# Un_51_V2_0.net
KiCad netlist of a schematic drawn in EAGLE
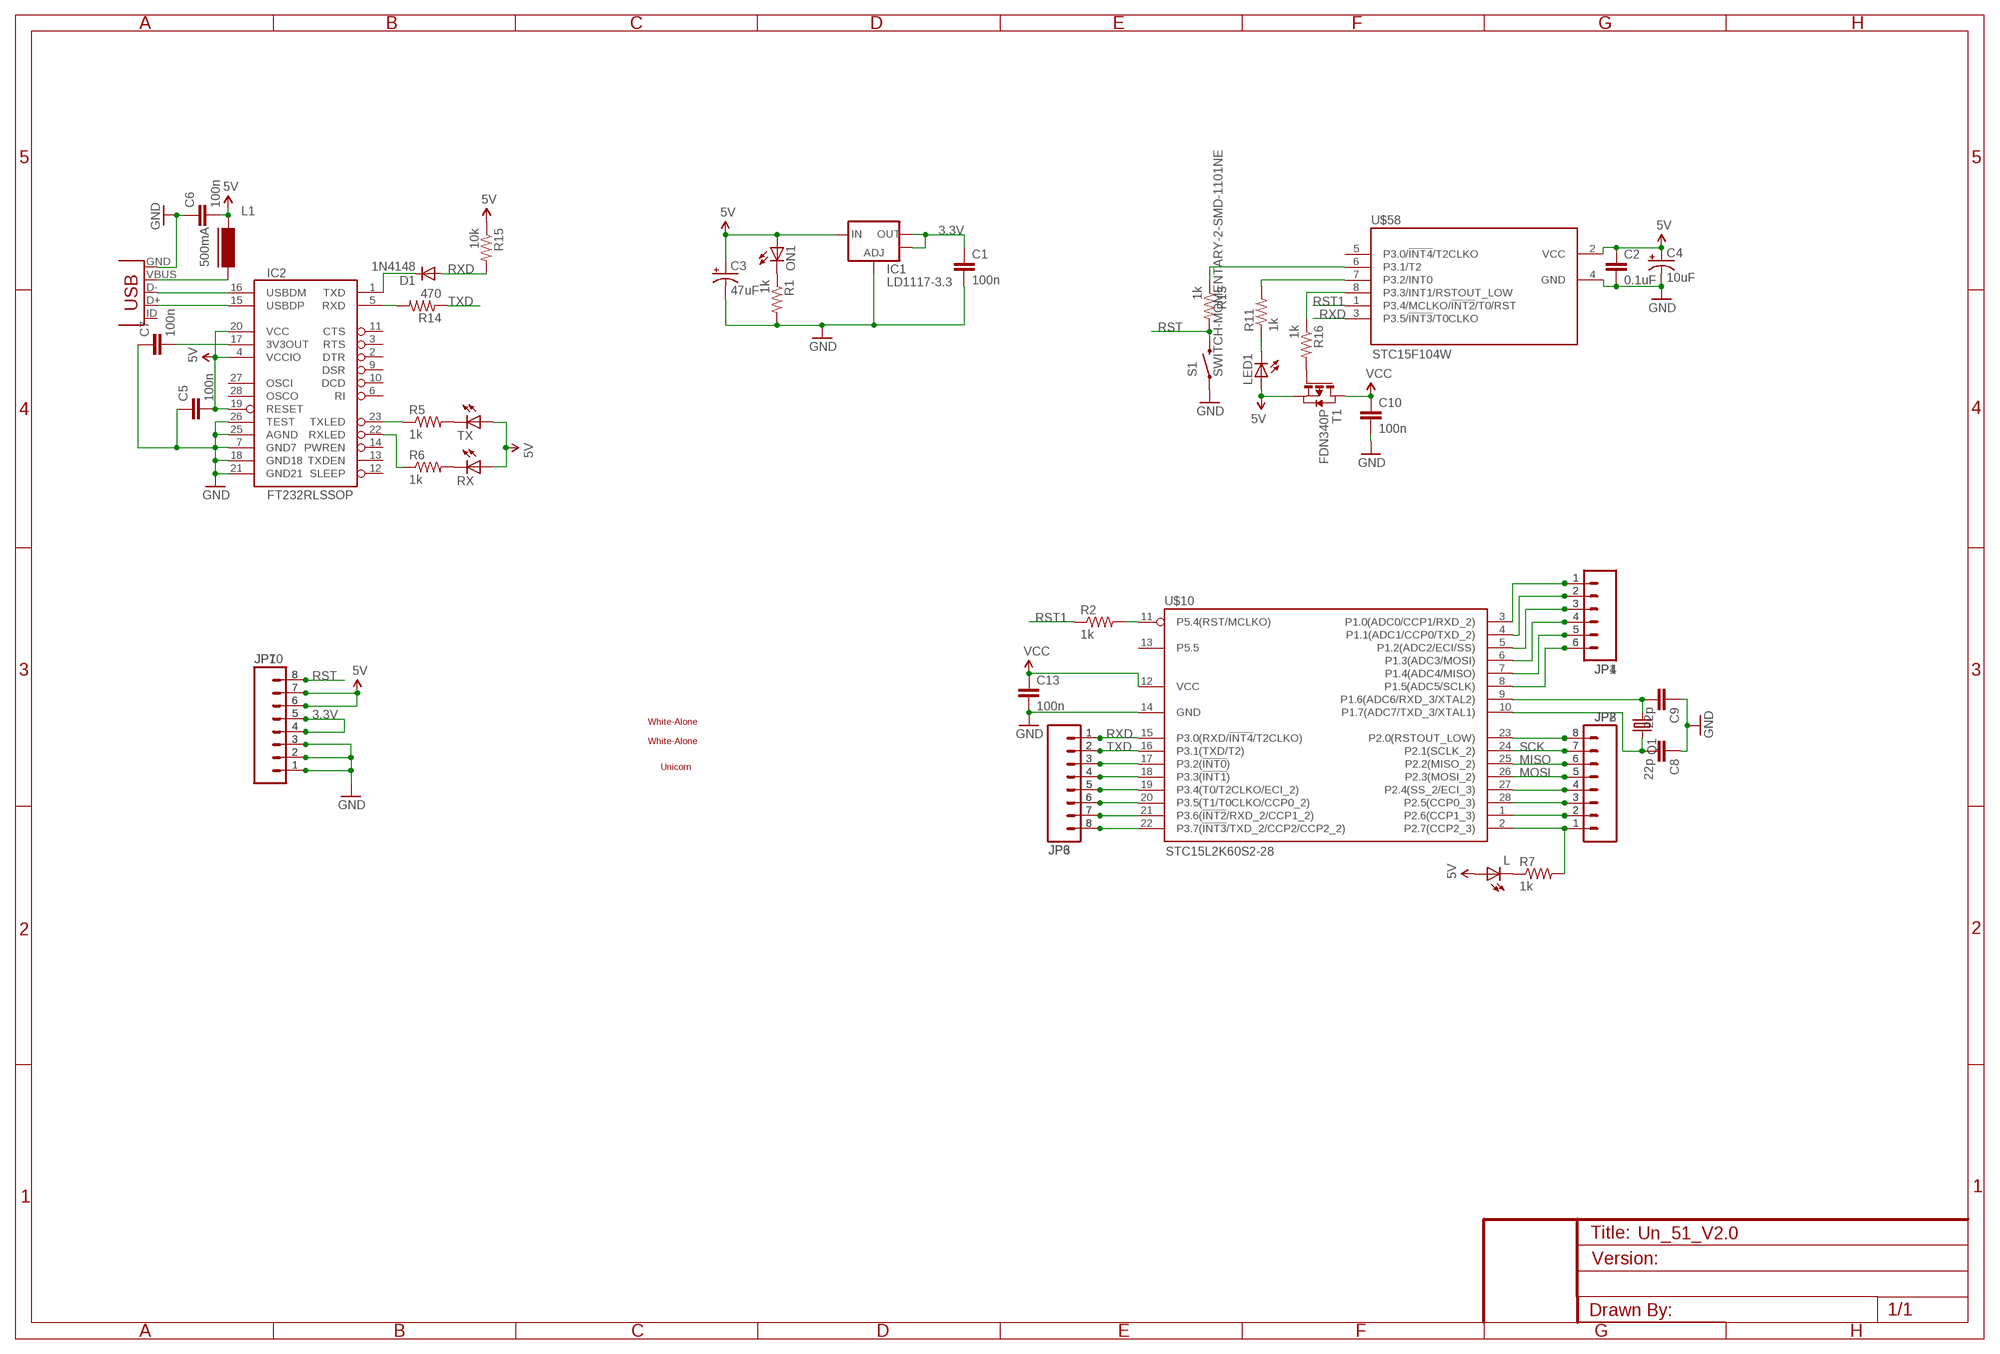
[diagram p0: schematic, sheet 1]

(export (version "E")
  (design (tool "Eeschema 10.0.6"))
  (components
    (comp (ref "C1")
      (value "100n")
      (footprint "eagle-import:0603-CAP")
      (libsource (lib "eagle-import") (part "2SparkFun_CAP0603-CAP"))
    )
    (comp (ref "C2")
      (value "0.1uF")
      (footprint "eagle-import:0603-CAP")
      (libsource (lib "eagle-import") (part "2SparkFun_CAP0603-CAP"))
    )
    (comp (ref "C3")
      (value "47uF")
      (footprint "eagle-import:PANASONIC_D")
      (libsource (lib "eagle-import") (part "CAP_POLD"))
    )
    (comp (ref "C4")
      (value "10uF")
      (footprint "eagle-import:EIA3216")
      (libsource (lib "eagle-import") (part "CAP_POL1206"))
    )
    (comp (ref "C5")
      (value "100n")
      (footprint "eagle-import:0603-CAP")
      (libsource (lib "eagle-import") (part "2SparkFun_CAP0603-CAP"))
    )
    (comp (ref "C6")
      (value "100n")
      (footprint "eagle-import:0603-CAP")
      (libsource (lib "eagle-import") (part "2SparkFun_CAP0603-CAP"))
    )
    (comp (ref "C7")
      (value "100n")
      (footprint "eagle-import:0603-CAP")
      (libsource (lib "eagle-import") (part "2SparkFun_CAP0603-CAP"))
    )
    (comp (ref "C8")
      (value "22p")
      (footprint "eagle-import:0603-CAP")
      (libsource (lib "eagle-import") (part "2SparkFun_CAP0603-CAP"))
    )
    (comp (ref "C9")
      (value "22p")
      (footprint "eagle-import:0603-CAP")
      (libsource (lib "eagle-import") (part "2SparkFun_CAP0603-CAP"))
    )
    (comp (ref "C10")
      (value "100n")
      (footprint "eagle-import:0603-CAP")
      (libsource (lib "eagle-import") (part "2SparkFun_CAP0603-CAP"))
    )
    (comp (ref "C13")
      (value "100n")
      (footprint "eagle-import:0603-CAP")
      (libsource (lib "eagle-import") (part "CAP0603-CAP"))
    )
    (comp (ref "D1")
      (value "1N4148")
      (footprint "eagle-import:SOD-323")
      (libsource (lib "eagle-import") (part "DIODESOD"))
    )
    (comp (ref "IC1")
      (value "LD1117-3.3")
      (footprint "eagle-import:SOT223")
      (libsource (lib "eagle-import") (part "V_REG_LM1117SOT223"))
    )
    (comp (ref "IC2")
      (value "FT232RLSSOP")
      (footprint "eagle-import:SSOP28DB")
      (libsource (lib "eagle-import") (part "FT232RLSSOP"))
    )
    (comp (ref "JP1")
      (value "M06SIP")
      (footprint "eagle-import:1X06")
      (libsource (lib "eagle-import") (part "M06SIP"))
    )
    (comp (ref "JP2")
      (value "M08")
      (footprint "eagle-import:1X08")
      (libsource (lib "eagle-import") (part "M08"))
    )
    (comp (ref "JP3")
      (value "M08")
      (footprint "eagle-import:1X08")
      (libsource (lib "eagle-import") (part "M08"))
    )
    (comp (ref "JP4")
      (value "M06SIP")
      (footprint "eagle-import:1X06")
      (libsource (lib "eagle-import") (part "M06SIP"))
    )
    (comp (ref "JP6")
      (value "M08")
      (footprint "eagle-import:1X08")
      (libsource (lib "eagle-import") (part "M08"))
    )
    (comp (ref "JP7")
      (value "M08")
      (footprint "eagle-import:1X08")
      (libsource (lib "eagle-import") (part "M08"))
    )
    (comp (ref "JP8")
      (value "M08")
      (footprint "eagle-import:1X08")
      (libsource (lib "eagle-import") (part "M08"))
    )
    (comp (ref "JP10")
      (value "M08")
      (footprint "eagle-import:1X08")
      (libsource (lib "eagle-import") (part "M08"))
    )
    (comp (ref "L")
      (value "LED0805")
      (footprint "eagle-import:LED-0805")
      (libsource (lib "eagle-import") (part "LED0805"))
    )
    (comp (ref "L1")
      (value "500mA")
      (footprint "eagle-import:FB805")
      (libsource (lib "eagle-import") (part "FERRITE-0805"))
    )
    (comp (ref "LED1")
      (value "LED0805")
      (footprint "eagle-import:LED-0805")
      (libsource (lib "eagle-import") (part "2SparkFun_LED0805"))
    )
    (comp (ref "ON1")
      (value "LED0805")
      (footprint "eagle-import:LED-0805")
      (libsource (lib "eagle-import") (part "LED0805"))
    )
    (comp (ref "Q1")
      (value "CRYSTALHC49US")
      (footprint "eagle-import:HC49US")
      (libsource (lib "eagle-import") (part "CRYSTALHC49US"))
    )
    (comp (ref "R1")
      (value "1k")
      (footprint "eagle-import:0603-RES")
      (libsource (lib "eagle-import") (part "RESISTOR0603-RES"))
    )
    (comp (ref "R2")
      (value "1k")
      (footprint "eagle-import:0603-RES")
      (libsource (lib "eagle-import") (part "RESISTOR0603-RES"))
    )
    (comp (ref "R5")
      (value "1k")
      (footprint "eagle-import:0603-RES")
      (libsource (lib "eagle-import") (part "RESISTOR0603-RES"))
    )
    (comp (ref "R6")
      (value "1k")
      (footprint "eagle-import:0603-RES")
      (libsource (lib "eagle-import") (part "RESISTOR0603-RES"))
    )
    (comp (ref "R7")
      (value "1k")
      (footprint "eagle-import:0603-RES")
      (libsource (lib "eagle-import") (part "RESISTOR0603-RES"))
    )
    (comp (ref "R11")
      (value "1k")
      (footprint "eagle-import:0603-RES")
      (libsource (lib "eagle-import") (part "RESISTOR0603-RES"))
    )
    (comp (ref "R13")
      (value "1k")
      (footprint "eagle-import:0603-RES")
      (libsource (lib "eagle-import") (part "RESISTOR0603-RES"))
    )
    (comp (ref "R14")
      (value "470")
      (footprint "eagle-import:0603-RES")
      (libsource (lib "eagle-import") (part "RESISTOR0603-RES"))
    )
    (comp (ref "R15")
      (value "10k")
      (footprint "eagle-import:0603-RES")
      (libsource (lib "eagle-import") (part "RESISTOR0603-RES"))
    )
    (comp (ref "R16")
      (value "1k")
      (footprint "eagle-import:0603-RES")
      (libsource (lib "eagle-import") (part "RESISTOR0603-RES"))
    )
    (comp (ref "RX")
      (value "LED0805")
      (footprint "eagle-import:LED-0805")
      (libsource (lib "eagle-import") (part "LED0805"))
    )
    (comp (ref "S1")
      (value "SWITCH-MOMENTARY-2-SMD-1101NE")
      (footprint "eagle-import:TACTILE-SWITCH-1101NE")
      (libsource (lib "eagle-import") (part "SWITCH-MOMENTARY-2-SMD-1101NE"))
    )
    (comp (ref "T1")
      (value "FDN340P")
      (footprint "eagle-import:SOT-23")
      (libsource (lib "eagle-import") (part "PMOSSOT23"))
    )
    (comp (ref "TX")
      (value "LED0805")
      (footprint "eagle-import:LED-0805")
      (libsource (lib "eagle-import") (part "LED0805"))
    )
    (comp (ref "U$3")
      (value "UNICORN_1")
      (footprint "eagle-import:UNICORN_1")
      (libsource (lib "eagle-import") (part "UNICORN_1"))
    )
    (comp (ref "U$7")
      (value "WHITE-ALONE_0")
      (footprint "eagle-import:WHITE-ALONE_0")
      (libsource (lib "eagle-import") (part "WHITE-ALONE_0"))
    )
    (comp (ref "U$10")
      (value "STC15L2K60S2-28")
      (footprint "eagle-import:SO-28W")
      (libsource (lib "eagle-import") (part "STC15L2K60S2-28"))
    )
    (comp (ref "U$11")
      (value "WHITE-ALONE_0")
      (footprint "eagle-import:WHITE-ALONE_0")
      (libsource (lib "eagle-import") (part "WHITE-ALONE_0"))
    )
    (comp (ref "U$58")
      (value "STC15F104W")
      (footprint "eagle-import:SO08")
      (libsource (lib "eagle-import") (part "STC15F104W"))
    )
    (comp (ref "X2")
      (value "USBSMD")
      (footprint "eagle-import:USB-MINIB")
      (libsource (lib "eagle-import") (part "USBSMD"))
    )
  )
  (nets
    (net (code "1") (name "/3.3V") (class "Default")
      (node (ref "C1") (pin "1") (pinfunction "1_1") (pintype "passive"))
      (node (ref "IC1") (pin "2") (pinfunction "OUT_2") (pintype "output"))
      (node (ref "IC1") (pin "4") (pinfunction "OUT_4") (pintype "output"))
      (node (ref "JP10") (pin "4") (pinfunction "4_4") (pintype "passive"))
      (node (ref "JP10") (pin "5") (pinfunction "5_5") (pintype "passive"))
      (node (ref "JP7") (pin "4") (pinfunction "4_4") (pintype "passive"))
      (node (ref "JP7") (pin "5") (pinfunction "5_5") (pintype "passive"))
    )
    (net (code "2") (name "/MISO") (class "Default")
      (node (ref "JP2") (pin "6") (pinfunction "6_6") (pintype "passive"))
      (node (ref "JP8") (pin "6") (pinfunction "6_6") (pintype "passive"))
      (node (ref "U$10") (pin "25") (pinfunction "P2.2(MISO_2)_25") (pintype "bidirectional"))
    )
    (net (code "3") (name "/MOSI") (class "Default")
      (node (ref "JP2") (pin "5") (pinfunction "5_5") (pintype "passive"))
      (node (ref "JP8") (pin "5") (pinfunction "5_5") (pintype "passive"))
      (node (ref "U$10") (pin "26") (pinfunction "P2.3(MOSI_2)_26") (pintype "bidirectional"))
    )
    (net (code "4") (name "/RST") (class "Default")
      (node (ref "JP10") (pin "8") (pinfunction "8_8") (pintype "passive"))
      (node (ref "JP7") (pin "8") (pinfunction "8_8") (pintype "passive"))
      (node (ref "R13") (pin "2") (pinfunction "2_2") (pintype "passive"))
      (node (ref "S1") (pin "P$2") (pinfunction "2_P$2") (pintype "passive"))
    )
    (net (code "5") (name "/RST1") (class "Default")
      (node (ref "R2") (pin "1") (pinfunction "1_1") (pintype "passive"))
      (node (ref "U$58") (pin "1") (pinfunction "P3.4/MCLKO/~{INT2}/T0/RST_1") (pintype "bidirectional"))
    )
    (net (code "6") (name "/RXD") (class "Default")
      (node (ref "D1") (pin "2") (pinfunction "A_2") (pintype "passive"))
      (node (ref "JP3") (pin "1") (pinfunction "1_1") (pintype "passive"))
      (node (ref "JP6") (pin "1") (pinfunction "1_1") (pintype "passive"))
      (node (ref "R15") (pin "2") (pinfunction "2_2") (pintype "passive"))
      (node (ref "U$10") (pin "15") (pinfunction "P3.0(RXD/~{INT4}/T2CLKO)_15") (pintype "bidirectional"))
      (node (ref "U$58") (pin "3") (pinfunction "P3.5/~{INT3}/T0CLKO_3") (pintype "bidirectional"))
    )
    (net (code "7") (name "/SCK") (class "Default")
      (node (ref "JP2") (pin "7") (pinfunction "7_7") (pintype "passive"))
      (node (ref "JP8") (pin "7") (pinfunction "7_7") (pintype "passive"))
      (node (ref "U$10") (pin "24") (pinfunction "P2.1(SCLK_2)_24") (pintype "bidirectional"))
    )
    (net (code "8") (name "/TXD") (class "Default")
      (node (ref "JP3") (pin "2") (pinfunction "2_2") (pintype "passive"))
      (node (ref "JP6") (pin "2") (pinfunction "2_2") (pintype "passive"))
      (node (ref "R14") (pin "1") (pinfunction "1_1") (pintype "passive"))
      (node (ref "U$10") (pin "16") (pinfunction "P3.1(TXD/T2)_16") (pintype "bidirectional"))
    )
    (net (code "9") (name "5V") (class "Default")
      (node (ref "C2") (pin "1") (pinfunction "1_1") (pintype "passive"))
      (node (ref "C3") (pin "+") (pinfunction "+_+") (pintype "passive"))
      (node (ref "C4") (pin "A") (pinfunction "+_A") (pintype "passive"))
      (node (ref "C5") (pin "2") (pinfunction "2_2") (pintype "passive"))
      (node (ref "C6") (pin "2") (pinfunction "2_2") (pintype "passive"))
      (node (ref "IC1") (pin "3") (pinfunction "IN_3") (pintype "input"))
      (node (ref "IC2") (pin "19") (pinfunction "RESET_19") (pintype "input"))
      (node (ref "IC2") (pin "20") (pinfunction "VCC_20") (pintype "power_in"))
      (node (ref "IC2") (pin "4") (pinfunction "VCCIO_4") (pintype "power_in"))
      (node (ref "JP10") (pin "6") (pinfunction "6_6") (pintype "passive"))
      (node (ref "JP10") (pin "7") (pinfunction "7_7") (pintype "passive"))
      (node (ref "JP7") (pin "6") (pinfunction "6_6") (pintype "passive"))
      (node (ref "JP7") (pin "7") (pinfunction "7_7") (pintype "passive"))
      (node (ref "L") (pin "1") (pinfunction "A_1") (pintype "passive"))
      (node (ref "L1") (pin "1") (pinfunction "1_1") (pintype "passive"))
      (node (ref "LED1") (pin "1") (pinfunction "A_1") (pintype "passive"))
      (node (ref "ON1") (pin "1") (pinfunction "A_1") (pintype "passive"))
      (node (ref "R15") (pin "1") (pinfunction "1_1") (pintype "passive"))
      (node (ref "RX") (pin "1") (pinfunction "A_1") (pintype "passive"))
      (node (ref "T1") (pin "2") (pinfunction "S_2") (pintype "passive"))
      (node (ref "TX") (pin "1") (pinfunction "A_1") (pintype "passive"))
      (node (ref "U$58") (pin "2") (pinfunction "VCC_2") (pintype "bidirectional"))
    )
    (net (code "10") (name "GND") (class "Default")
      (node (ref "C1") (pin "2") (pinfunction "2_2") (pintype "passive"))
      (node (ref "C10") (pin "2") (pinfunction "2_2") (pintype "passive"))
      (node (ref "C13") (pin "2") (pinfunction "2_2") (pintype "passive"))
      (node (ref "C2") (pin "2") (pinfunction "2_2") (pintype "passive"))
      (node (ref "C3") (pin "-") (pinfunction "-_-") (pintype "passive"))
      (node (ref "C4") (pin "C") (pinfunction "-_C") (pintype "passive"))
      (node (ref "C5") (pin "1") (pinfunction "1_1") (pintype "passive"))
      (node (ref "C6") (pin "1") (pinfunction "1_1") (pintype "passive"))
      (node (ref "C7") (pin "1") (pinfunction "1_1") (pintype "passive"))
      (node (ref "C8") (pin "1") (pinfunction "1_1") (pintype "passive"))
      (node (ref "C9") (pin "1") (pinfunction "1_1") (pintype "passive"))
      (node (ref "IC1") (pin "1") (pinfunction "ADJ_1") (pintype "input"))
      (node (ref "IC2") (pin "18") (pinfunction "GND18_18") (pintype "power_in"))
      (node (ref "IC2") (pin "21") (pinfunction "GND21_21") (pintype "power_in"))
      (node (ref "IC2") (pin "25") (pinfunction "AGND_25") (pintype "power_in"))
      (node (ref "IC2") (pin "26") (pinfunction "TEST_26") (pintype "input"))
      (node (ref "IC2") (pin "7") (pinfunction "GND7_7") (pintype "power_in"))
      (node (ref "JP10") (pin "1") (pinfunction "1_1") (pintype "passive"))
      (node (ref "JP10") (pin "2") (pinfunction "2_2") (pintype "passive"))
      (node (ref "JP10") (pin "3") (pinfunction "3_3") (pintype "passive"))
      (node (ref "JP7") (pin "1") (pinfunction "1_1") (pintype "passive"))
      (node (ref "JP7") (pin "2") (pinfunction "2_2") (pintype "passive"))
      (node (ref "JP7") (pin "3") (pinfunction "3_3") (pintype "passive"))
      (node (ref "R1") (pin "2") (pinfunction "2_2") (pintype "passive"))
      (node (ref "S1") (pin "P$1") (pinfunction "1_P$1") (pintype "passive"))
      (node (ref "U$10") (pin "14") (pinfunction "GND_14") (pintype "bidirectional"))
      (node (ref "U$58") (pin "4") (pinfunction "GND_4") (pintype "bidirectional"))
      (node (ref "X2") (pin "GND") (pinfunction "GND_GND") (pintype "bidirectional"))
    )
    (net (code "11") (name "Net-(D1-C)") (class "Default")
      (node (ref "D1") (pin "1") (pinfunction "C_1") (pintype "passive"))
      (node (ref "IC2") (pin "1") (pinfunction "TXD_1") (pintype "output"))
    )
    (net (code "12") (name "Net-(IC2-3V3OUT)") (class "Default")
      (node (ref "C7") (pin "2") (pinfunction "2_2") (pintype "passive"))
      (node (ref "IC2") (pin "17") (pinfunction "3V3OUT_17") (pintype "output"))
    )
    (net (code "13") (name "Net-(IC2-RXD)") (class "Default")
      (node (ref "IC2") (pin "5") (pinfunction "RXD_5") (pintype "input"))
      (node (ref "R14") (pin "2") (pinfunction "2_2") (pintype "passive"))
    )
    (net (code "14") (name "Net-(IC2-RXLED)") (class "Default")
      (node (ref "IC2") (pin "22") (pinfunction "RXLED_22") (pintype "input"))
      (node (ref "R6") (pin "1") (pinfunction "1_1") (pintype "passive"))
    )
    (net (code "15") (name "Net-(IC2-TXLED)") (class "Default")
      (node (ref "IC2") (pin "23") (pinfunction "TXLED_23") (pintype "input"))
      (node (ref "R5") (pin "1") (pinfunction "1_1") (pintype "passive"))
    )
    (net (code "16") (name "Net-(IC2-USBDM)") (class "Default")
      (node (ref "IC2") (pin "16") (pinfunction "USBDM_16") (pintype "bidirectional"))
      (node (ref "X2") (pin "D-") (pinfunction "D-_D-") (pintype "bidirectional"))
    )
    (net (code "17") (name "Net-(IC2-USBDP)") (class "Default")
      (node (ref "IC2") (pin "15") (pinfunction "USBDP_15") (pintype "bidirectional"))
      (node (ref "X2") (pin "D+") (pinfunction "D+_D+") (pintype "bidirectional"))
    )
    (net (code "18") (name "Net-(L-C)") (class "Default")
      (node (ref "L") (pin "2") (pinfunction "C_2") (pintype "passive"))
      (node (ref "R7") (pin "1") (pinfunction "1_1") (pintype "passive"))
    )
    (net (code "19") (name "Net-(L1-Pad2)") (class "Default")
      (node (ref "L1") (pin "2") (pinfunction "2_2") (pintype "passive"))
      (node (ref "X2") (pin "VBUS") (pinfunction "VBUS_VBUS") (pintype "bidirectional"))
    )
    (net (code "20") (name "Net-(LED1-C)") (class "Default")
      (node (ref "LED1") (pin "2") (pinfunction "C_2") (pintype "passive"))
      (node (ref "R11") (pin "1") (pinfunction "1_1") (pintype "passive"))
    )
    (net (code "21") (name "Net-(ON1-C)") (class "Default")
      (node (ref "ON1") (pin "2") (pinfunction "C_2") (pintype "passive"))
      (node (ref "R1") (pin "1") (pinfunction "1_1") (pintype "passive"))
    )
    (net (code "22") (name "Net-(RX-C)") (class "Default")
      (node (ref "R6") (pin "2") (pinfunction "2_2") (pintype "passive"))
      (node (ref "RX") (pin "2") (pinfunction "C_2") (pintype "passive"))
    )
    (net (code "23") (name "Net-(T1-G)") (class "Default")
      (node (ref "R16") (pin "2") (pinfunction "2_2") (pintype "passive"))
      (node (ref "T1") (pin "3") (pinfunction "G_3") (pintype "passive"))
    )
    (net (code "24") (name "Net-(TX-C)") (class "Default")
      (node (ref "R5") (pin "2") (pinfunction "2_2") (pintype "passive"))
      (node (ref "TX") (pin "2") (pinfunction "C_2") (pintype "passive"))
    )
    (net (code "25") (name "Net-(U$10-P1.0(ADC0{slash}CCP1{slash}RXD_2))") (class "Default")
      (node (ref "JP1") (pin "1") (pinfunction "1_1") (pintype "passive"))
      (node (ref "JP4") (pin "1") (pinfunction "1_1") (pintype "passive"))
      (node (ref "U$10") (pin "3") (pinfunction "P1.0(ADC0/CCP1/RXD_2)_3") (pintype "bidirectional"))
    )
    (net (code "26") (name "Net-(U$10-P1.1(ADC1{slash}CCP0{slash}TXD_2))") (class "Default")
      (node (ref "JP1") (pin "2") (pinfunction "2_2") (pintype "passive"))
      (node (ref "JP4") (pin "2") (pinfunction "2_2") (pintype "passive"))
      (node (ref "U$10") (pin "4") (pinfunction "P1.1(ADC1/CCP0/TXD_2)_4") (pintype "bidirectional"))
    )
    (net (code "27") (name "Net-(U$10-P1.2(ADC2{slash}ECI{slash}SS))") (class "Default")
      (node (ref "JP1") (pin "3") (pinfunction "3_3") (pintype "passive"))
      (node (ref "JP4") (pin "3") (pinfunction "3_3") (pintype "passive"))
      (node (ref "U$10") (pin "5") (pinfunction "P1.2(ADC2/ECI/SS)_5") (pintype "bidirectional"))
    )
    (net (code "28") (name "Net-(U$10-P1.3(ADC3{slash}MOSI))") (class "Default")
      (node (ref "JP1") (pin "4") (pinfunction "4_4") (pintype "passive"))
      (node (ref "JP4") (pin "4") (pinfunction "4_4") (pintype "passive"))
      (node (ref "U$10") (pin "6") (pinfunction "P1.3(ADC3/MOSI)_6") (pintype "bidirectional"))
    )
    (net (code "29") (name "Net-(U$10-P1.4(ADC4{slash}MISO))") (class "Default")
      (node (ref "JP1") (pin "5") (pinfunction "5_5") (pintype "passive"))
      (node (ref "JP4") (pin "5") (pinfunction "5_5") (pintype "passive"))
      (node (ref "U$10") (pin "7") (pinfunction "P1.4(ADC4/MISO)_7") (pintype "bidirectional"))
    )
    (net (code "30") (name "Net-(U$10-P1.5(ADC5{slash}SCLK))") (class "Default")
      (node (ref "JP1") (pin "6") (pinfunction "6_6") (pintype "passive"))
      (node (ref "JP4") (pin "6") (pinfunction "6_6") (pintype "passive"))
      (node (ref "U$10") (pin "8") (pinfunction "P1.5(ADC5/SCLK)_8") (pintype "bidirectional"))
    )
    (net (code "31") (name "Net-(U$10-P1.6(ADC6{slash}RXD_3{slash}XTAL2))") (class "Default")
      (node (ref "C9") (pin "2") (pinfunction "2_2") (pintype "passive"))
      (node (ref "Q1") (pin "1") (pinfunction "1_1") (pintype "passive"))
      (node (ref "U$10") (pin "9") (pinfunction "P1.6(ADC6/RXD_3/XTAL2)_9") (pintype "bidirectional"))
    )
    (net (code "32") (name "Net-(U$10-P1.7(ADC7{slash}TXD_3{slash}XTAL1))") (class "Default")
      (node (ref "C8") (pin "2") (pinfunction "2_2") (pintype "passive"))
      (node (ref "Q1") (pin "2") (pinfunction "2_2") (pintype "passive"))
      (node (ref "U$10") (pin "10") (pinfunction "P1.7(ADC7/TXD_3/XTAL1)_10") (pintype "bidirectional"))
    )
    (net (code "33") (name "Net-(U$10-P2.0(RSTOUT_LOW))") (class "Default")
      (node (ref "JP2") (pin "8") (pinfunction "8_8") (pintype "passive"))
      (node (ref "JP8") (pin "8") (pinfunction "8_8") (pintype "passive"))
      (node (ref "U$10") (pin "23") (pinfunction "P2.0(RSTOUT_LOW)_23") (pintype "bidirectional"))
    )
    (net (code "34") (name "Net-(U$10-P2.4(SS_2{slash}ECI_3))") (class "Default")
      (node (ref "JP2") (pin "4") (pinfunction "4_4") (pintype "passive"))
      (node (ref "JP8") (pin "4") (pinfunction "4_4") (pintype "passive"))
      (node (ref "U$10") (pin "27") (pinfunction "P2.4(SS_2/ECI_3)_27") (pintype "bidirectional"))
    )
    (net (code "35") (name "Net-(U$10-P2.5(CCP0_3))") (class "Default")
      (node (ref "JP2") (pin "3") (pinfunction "3_3") (pintype "passive"))
      (node (ref "JP8") (pin "3") (pinfunction "3_3") (pintype "passive"))
      (node (ref "U$10") (pin "28") (pinfunction "P2.5(CCP0_3)_28") (pintype "bidirectional"))
    )
    (net (code "36") (name "Net-(U$10-P2.6(CCP1_3))") (class "Default")
      (node (ref "JP2") (pin "2") (pinfunction "2_2") (pintype "passive"))
      (node (ref "JP8") (pin "2") (pinfunction "2_2") (pintype "passive"))
      (node (ref "U$10") (pin "1") (pinfunction "P2.6(CCP1_3)_1") (pintype "bidirectional"))
    )
    (net (code "37") (name "Net-(U$10-P2.7(CCP2_3))") (class "Default")
      (node (ref "JP2") (pin "1") (pinfunction "1_1") (pintype "passive"))
      (node (ref "JP8") (pin "1") (pinfunction "1_1") (pintype "passive"))
      (node (ref "R7") (pin "2") (pinfunction "2_2") (pintype "passive"))
      (node (ref "U$10") (pin "2") (pinfunction "P2.7(CCP2_3)_2") (pintype "bidirectional"))
    )
    (net (code "38") (name "Net-(U$10-P3.2(~{INT0}))") (class "Default")
      (node (ref "JP3") (pin "3") (pinfunction "3_3") (pintype "passive"))
      (node (ref "JP6") (pin "3") (pinfunction "3_3") (pintype "passive"))
      (node (ref "U$10") (pin "17") (pinfunction "P3.2(~{INT0})_17") (pintype "bidirectional"))
    )
    (net (code "39") (name "Net-(U$10-P3.3(~{INT1}))") (class "Default")
      (node (ref "JP3") (pin "4") (pinfunction "4_4") (pintype "passive"))
      (node (ref "JP6") (pin "4") (pinfunction "4_4") (pintype "passive"))
      (node (ref "U$10") (pin "18") (pinfunction "P3.3(~{INT1})_18") (pintype "bidirectional"))
    )
    (net (code "40") (name "Net-(U$10-P3.4(T0{slash}T2CLKO{slash}ECI_2))") (class "Default")
      (node (ref "JP3") (pin "5") (pinfunction "5_5") (pintype "passive"))
      (node (ref "JP6") (pin "5") (pinfunction "5_5") (pintype "passive"))
      (node (ref "U$10") (pin "19") (pinfunction "P3.4(T0/T2CLKO/ECI_2)_19") (pintype "bidirectional"))
    )
    (net (code "41") (name "Net-(U$10-P3.5(T1{slash}T0CLKO{slash}CCP0_2))") (class "Default")
      (node (ref "JP3") (pin "6") (pinfunction "6_6") (pintype "passive"))
      (node (ref "JP6") (pin "6") (pinfunction "6_6") (pintype "passive"))
      (node (ref "U$10") (pin "20") (pinfunction "P3.5(T1/T0CLKO/CCP0_2)_20") (pintype "bidirectional"))
    )
    (net (code "42") (name "Net-(U$10-P3.6(~{INT2}{slash}RXD_2{slash}CCP1_2))") (class "Default")
      (node (ref "JP3") (pin "7") (pinfunction "7_7") (pintype "passive"))
      (node (ref "JP6") (pin "7") (pinfunction "7_7") (pintype "passive"))
      (node (ref "U$10") (pin "21") (pinfunction "P3.6(~{INT2}/RXD_2/CCP1_2)_21") (pintype "bidirectional"))
    )
    (net (code "43") (name "Net-(U$10-P3.7(~{INT3}{slash}TXD_2{slash}CCP2{slash}CCP2_2))") (class "Default")
      (node (ref "JP3") (pin "8") (pinfunction "8_8") (pintype "passive"))
      (node (ref "JP6") (pin "8") (pinfunction "8_8") (pintype "passive"))
      (node (ref "U$10") (pin "22") (pinfunction "P3.7(~{INT3}/TXD_2/CCP2/CCP2_2)_22") (pintype "bidirectional"))
    )
    (net (code "44") (name "Net-(U$10-P5.4(RST{slash}MCLKO))") (class "Default")
      (node (ref "R2") (pin "2") (pinfunction "2_2") (pintype "passive"))
      (node (ref "U$10") (pin "11") (pinfunction "P5.4(RST/MCLKO)_11") (pintype "bidirectional"))
    )
    (net (code "45") (name "Net-(U$58-P3.1{slash}T2)") (class "Default")
      (node (ref "R13") (pin "1") (pinfunction "1_1") (pintype "passive"))
      (node (ref "U$58") (pin "6") (pinfunction "P3.1/T2_6") (pintype "bidirectional"))
    )
    (net (code "46") (name "Net-(U$58-P3.2{slash}INT0)") (class "Default")
      (node (ref "R11") (pin "2") (pinfunction "2_2") (pintype "passive"))
      (node (ref "U$58") (pin "7") (pinfunction "P3.2/INT0_7") (pintype "bidirectional"))
    )
    (net (code "47") (name "Net-(U$58-P3.3{slash}INT1{slash}RSTOUT_LOW)") (class "Default")
      (node (ref "R16") (pin "1") (pinfunction "1_1") (pintype "passive"))
      (node (ref "U$58") (pin "8") (pinfunction "P3.3/INT1/RSTOUT_LOW_8") (pintype "bidirectional"))
    )
    (net (code "48") (name "VCC") (class "Default")
      (node (ref "C10") (pin "1") (pinfunction "1_1") (pintype "passive"))
      (node (ref "C13") (pin "1") (pinfunction "1_1") (pintype "passive"))
      (node (ref "T1") (pin "1") (pinfunction "D_1") (pintype "passive"))
      (node (ref "U$10") (pin "12") (pinfunction "VCC_12") (pintype "bidirectional"))
    )
    (net (code "49") (name "unconnected-(IC2-CTS-Pad11)") (class "Default")
      (node (ref "IC2") (pin "11") (pinfunction "CTS_11") (pintype "input"))
    )
    (net (code "50") (name "unconnected-(IC2-DCD-Pad10)") (class "Default")
      (node (ref "IC2") (pin "10") (pinfunction "DCD_10") (pintype "input"))
    )
    (net (code "51") (name "unconnected-(IC2-DSR-Pad9)") (class "Default")
      (node (ref "IC2") (pin "9") (pinfunction "DSR_9") (pintype "input"))
    )
    (net (code "52") (name "unconnected-(IC2-DTR-Pad2)") (class "Default")
      (node (ref "IC2") (pin "2") (pinfunction "DTR_2") (pintype "output"))
    )
    (net (code "53") (name "unconnected-(IC2-OSCI-Pad27)") (class "Default")
      (node (ref "IC2") (pin "27") (pinfunction "OSCI_27") (pintype "input"))
    )
    (net (code "54") (name "unconnected-(IC2-OSCO-Pad28)") (class "Default")
      (node (ref "IC2") (pin "28") (pinfunction "OSCO_28") (pintype "output"))
    )
    (net (code "55") (name "unconnected-(IC2-PWREN-Pad14)") (class "Default")
      (node (ref "IC2") (pin "14") (pinfunction "PWREN_14") (pintype "input"))
    )
    (net (code "56") (name "unconnected-(IC2-RI-Pad6)") (class "Default")
      (node (ref "IC2") (pin "6") (pinfunction "RI_6") (pintype "input"))
    )
    (net (code "57") (name "unconnected-(IC2-RTS-Pad3)") (class "Default")
      (node (ref "IC2") (pin "3") (pinfunction "RTS_3") (pintype "output"))
    )
    (net (code "58") (name "unconnected-(IC2-SLEEP-Pad12)") (class "Default")
      (node (ref "IC2") (pin "12") (pinfunction "SLEEP_12") (pintype "input"))
    )
    (net (code "59") (name "unconnected-(IC2-TXDEN-Pad13)") (class "Default")
      (node (ref "IC2") (pin "13") (pinfunction "TXDEN_13") (pintype "input"))
    )
    (net (code "60") (name "unconnected-(U$10-P5.5-Pad13)") (class "Default")
      (node (ref "U$10") (pin "13") (pinfunction "P5.5_13") (pintype "bidirectional"))
    )
    (net (code "61") (name "unconnected-(U$58-P3.0{slash}~{INT4}{slash}T2CLKO-Pad5)") (class "Default")
      (node (ref "U$58") (pin "5") (pinfunction "P3.0/~{INT4}/T2CLKO_5") (pintype "bidirectional"))
    )
    (net (code "62") (name "unconnected-(X2-USBID-PadID)") (class "Default")
      (node (ref "X2") (pin "ID") (pinfunction "USBID_ID") (pintype "bidirectional"))
    )
  )
)
